# design.net
KiCad netlist of a schematic drawn in Altium Designer
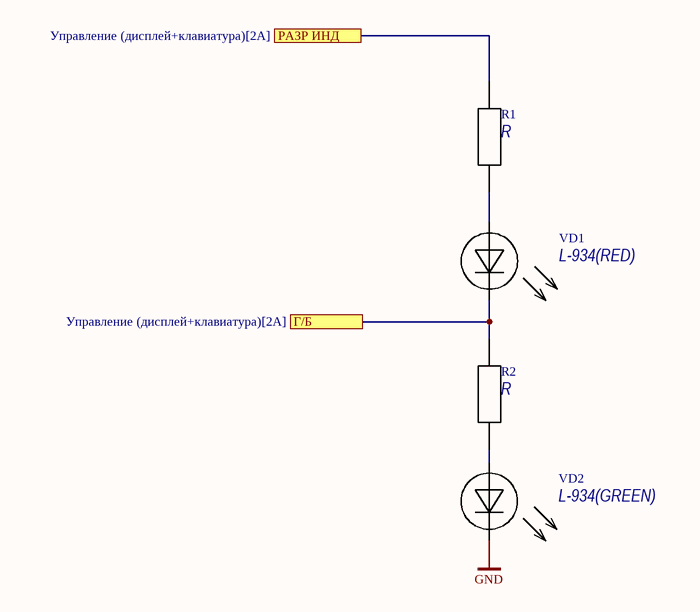
[diagram p0: Светодиоды.SchDoc]

(export (version "E")
  (design (tool "Eeschema 10.0.6"))
  (components
    (comp (ref "R1") (value "R") (footprint "R") (libsource (lib "UGO") (part "R")))
    (comp (ref "R2") (value "R") (footprint "R") (libsource (lib "UGO") (part "R")))
    (comp (ref "VD1")
      (value "L-934(RED)")
      (footprint "L-934(RED)")
      (libsource (lib "UGO") (part "L-934(RED)"))
    )
    (comp (ref "VD2")
      (value "L-934(GREEN)")
      (footprint "L-934(GREEN)")
      (libsource (lib "UGO") (part "L-934(GREEN)"))
    )
  )
  (nets
    (net (code "1") (name "/Г{slash}Б") (class "Default")
      (node (ref "R2") (pin "2") (pintype "passive"))
      (node (ref "VD1") (pin "2") (pintype "passive"))
    )
    (net (code "2") (name "/РАЗР ИНД") (class "Default") (node (ref "R1") (pin "2") (pintype "passive")))
    (net (code "3") (name "GND") (class "Default") (node (ref "VD2") (pin "2") (pintype "passive")))
    (net (code "4") (name "Net-(R1-Pad1)") (class "Default")
      (node (ref "R1") (pin "1") (pintype "passive"))
      (node (ref "VD1") (pin "1") (pintype "passive"))
    )
    (net (code "5") (name "Net-(R2-Pad1)") (class "Default")
      (node (ref "R2") (pin "1") (pintype "passive"))
      (node (ref "VD2") (pin "1") (pintype "passive"))
    )
  )
)
